# Mimi_layout.net
KiCad netlist of a schematic drawn in EAGLE
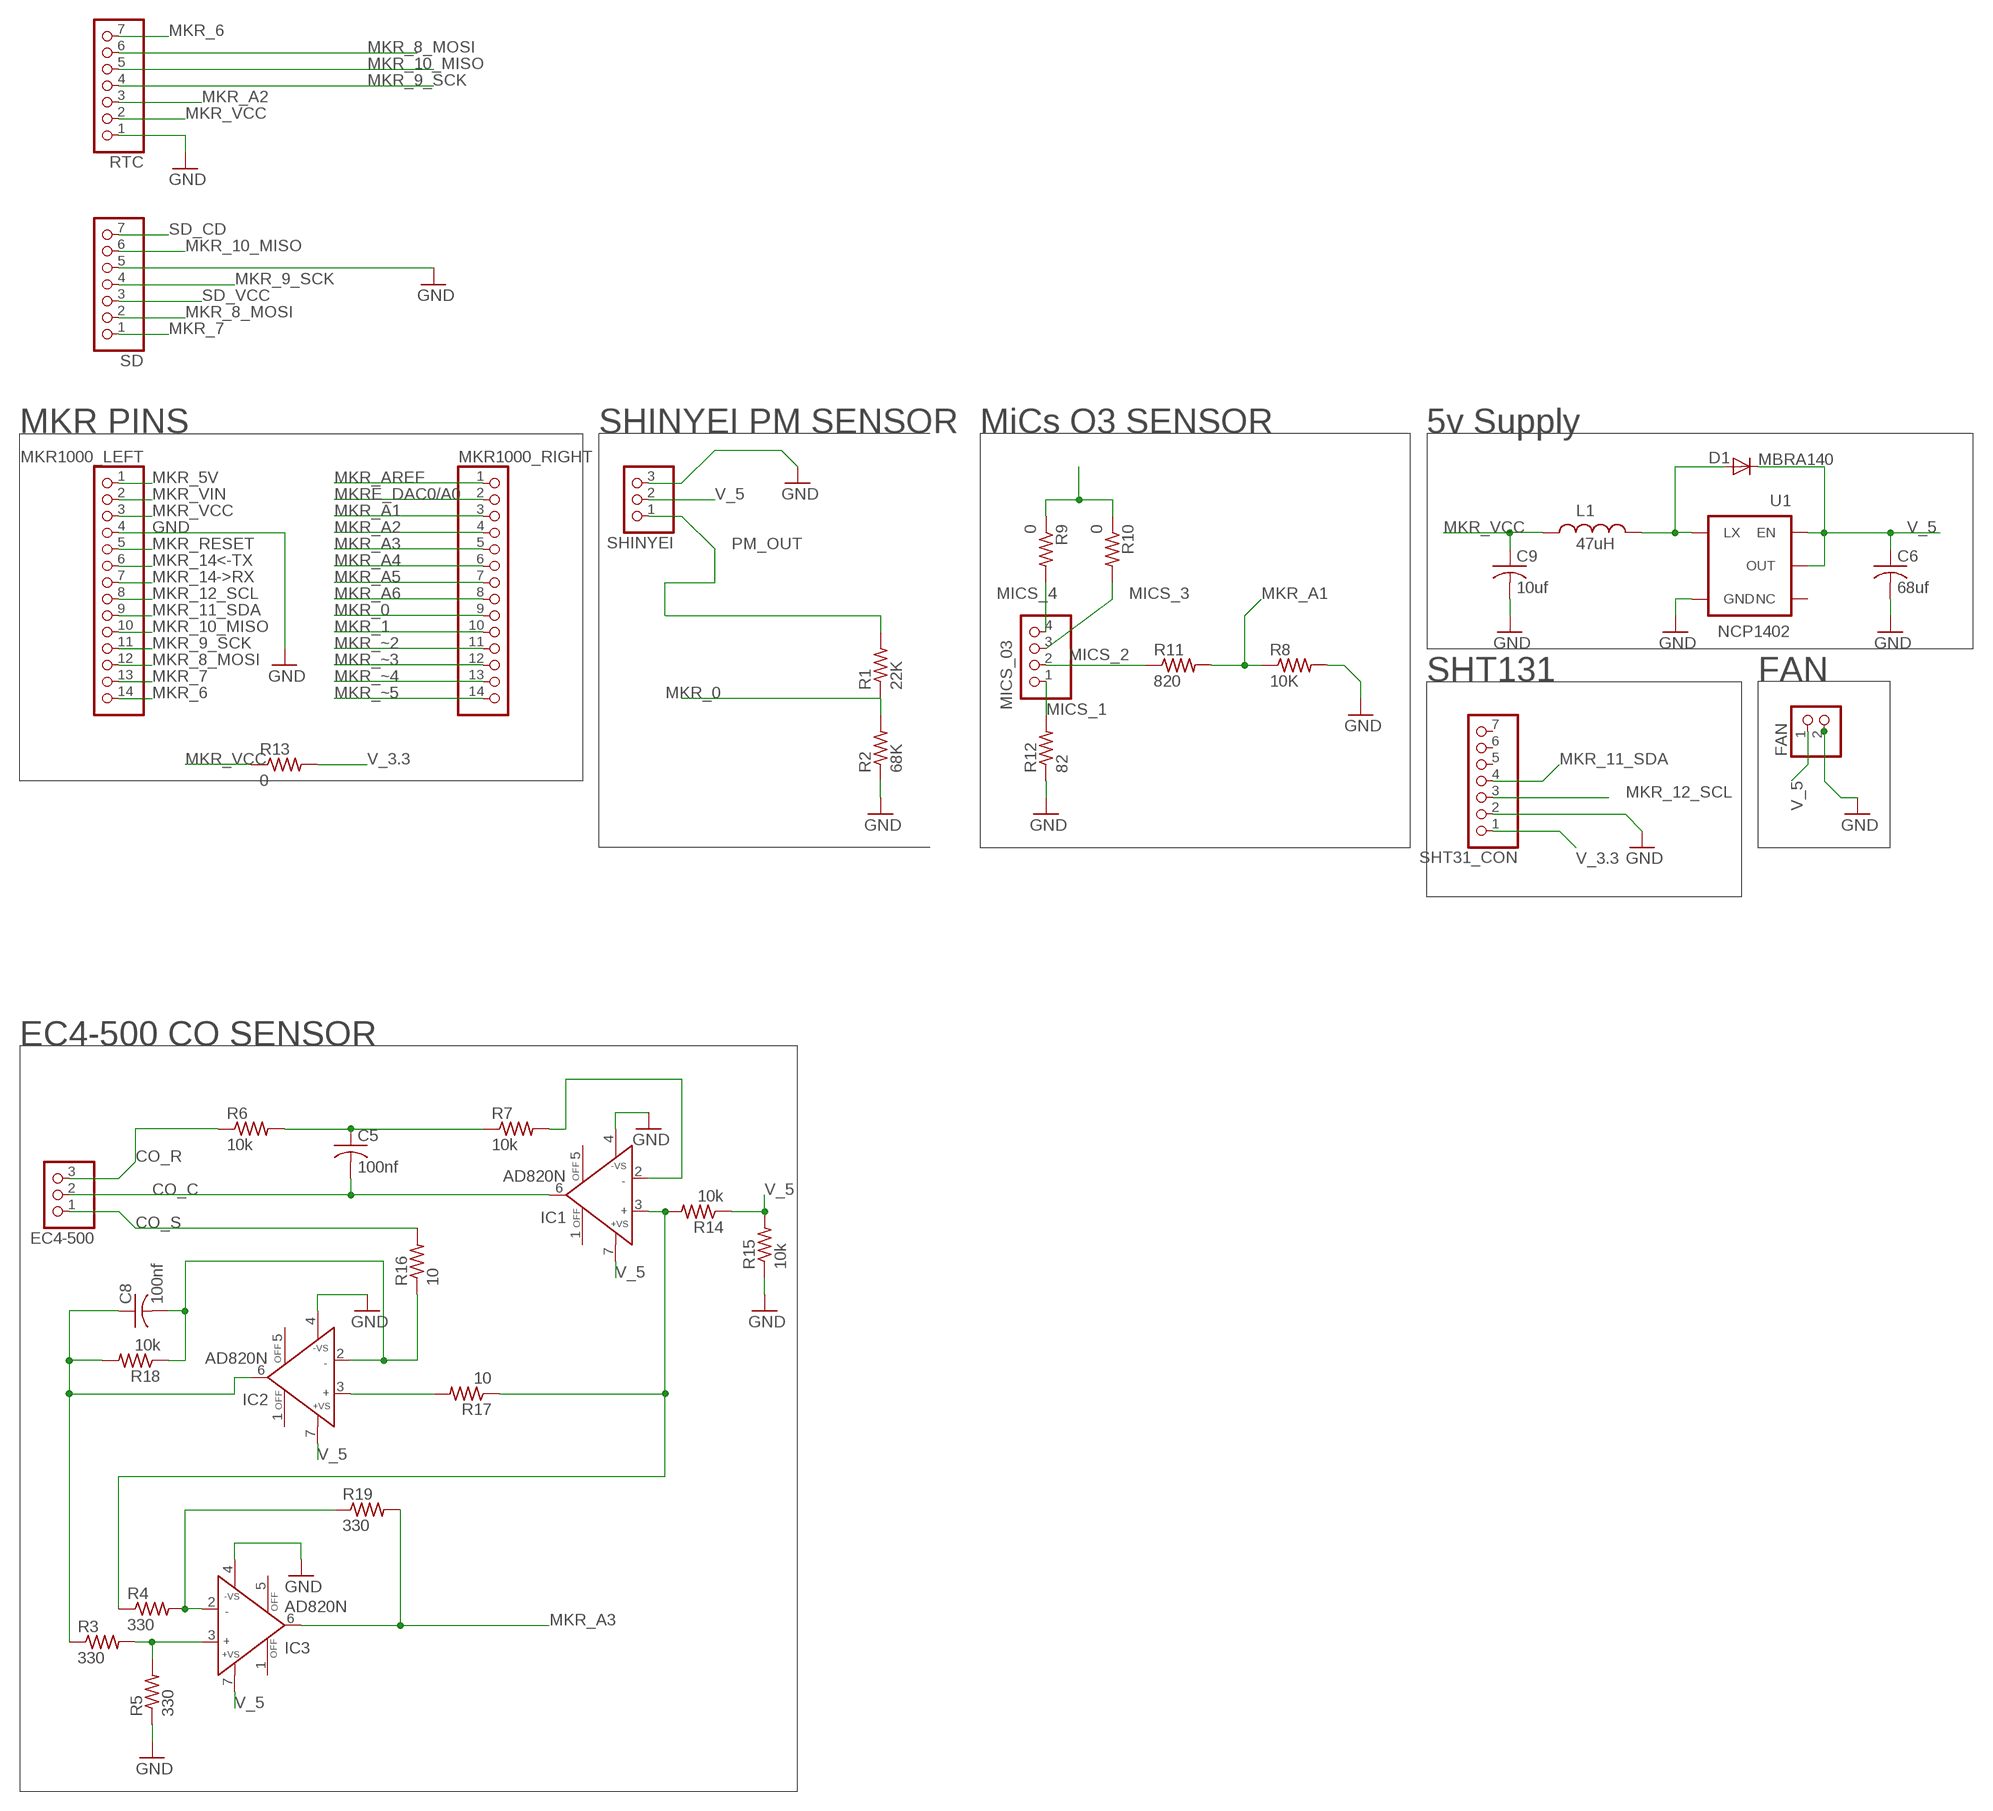
[diagram p0: schematic, sheet 1]

(export (version "E")
  (design (tool "Eeschema 10.0.6"))
  (components
    (comp (ref "C5")
      (value "100nf")
      (footprint "eagle-import:C0805")
      (libsource (lib "eagle-import") (part "C-USC0805"))
    )
    (comp (ref "C6")
      (value "68uf")
      (footprint "eagle-import:C0805")
      (libsource (lib "eagle-import") (part "C-USC0805"))
    )
    (comp (ref "C8")
      (value "100nf")
      (footprint "eagle-import:C0805")
      (libsource (lib "eagle-import") (part "C-USC0805"))
    )
    (comp (ref "C9")
      (value "10uf")
      (footprint "eagle-import:C0805")
      (libsource (lib "eagle-import") (part "C-USC0805"))
    )
    (comp (ref "D1")
      (value "MBRA140")
      (footprint "eagle-import:SMA-DIODE")
      (libsource (lib "eagle-import") (part "DIODESMA"))
    )
    (comp (ref "EC4-500")
      (value "PINHD-1X3")
      (footprint "eagle-import:1X03")
      (libsource (lib "eagle-import") (part "PINHD-1X3"))
    )
    (comp (ref "FAN")
      (value "PINHD-1X2")
      (footprint "eagle-import:1X02")
      (libsource (lib "eagle-import") (part "PINHD-1X2"))
    )
    (comp (ref "IC1")
      (value "AD820N")
      (footprint "eagle-import:DIL08")
      (libsource (lib "eagle-import") (part "AD820N"))
    )
    (comp (ref "IC2")
      (value "AD820N")
      (footprint "eagle-import:DIL08")
      (libsource (lib "eagle-import") (part "AD820N"))
    )
    (comp (ref "IC3")
      (value "AD820N")
      (footprint "eagle-import:DIL08")
      (libsource (lib "eagle-import") (part "AD820N"))
    )
    (comp (ref "L1")
      (value "47uH")
      (footprint "eagle-import:CR54")
      (libsource (lib "eagle-import") (part "INDUCTORCR54"))
    )
    (comp (ref "MICS_03")
      (value "PINHD-1X4")
      (footprint "eagle-import:1X04")
      (libsource (lib "eagle-import") (part "PINHD-1X4"))
    )
    (comp (ref "MKR1000_LEFT")
      (value "PINHD-1X14")
      (footprint "eagle-import:1X14")
      (libsource (lib "eagle-import") (part "PINHD-1X14"))
    )
    (comp (ref "MKR1000_RIGHT")
      (value "PINHD-1X14")
      (footprint "eagle-import:1X14")
      (libsource (lib "eagle-import") (part "PINHD-1X14"))
    )
    (comp (ref "R1")
      (value "22K")
      (footprint "eagle-import:R0805")
      (libsource (lib "eagle-import") (part "R-US_R0805"))
    )
    (comp (ref "R2")
      (value "68K")
      (footprint "eagle-import:R0805")
      (libsource (lib "eagle-import") (part "R-US_R0805"))
    )
    (comp (ref "R3")
      (value "330")
      (footprint "eagle-import:R0805")
      (libsource (lib "eagle-import") (part "R-US_R0805"))
    )
    (comp (ref "R4")
      (value "330")
      (footprint "eagle-import:R0805")
      (libsource (lib "eagle-import") (part "R-US_R0805"))
    )
    (comp (ref "R5")
      (value "330")
      (footprint "eagle-import:R0805")
      (libsource (lib "eagle-import") (part "R-US_R0805"))
    )
    (comp (ref "R6")
      (value "10k")
      (footprint "eagle-import:R0805")
      (libsource (lib "eagle-import") (part "R-US_R0805"))
    )
    (comp (ref "R7")
      (value "10k")
      (footprint "eagle-import:R0805")
      (libsource (lib "eagle-import") (part "R-US_R0805"))
    )
    (comp (ref "R8")
      (value "10K")
      (footprint "eagle-import:R0805")
      (libsource (lib "eagle-import") (part "R-US_R0805"))
    )
    (comp (ref "R9")
      (value "0")
      (footprint "eagle-import:R0805")
      (libsource (lib "eagle-import") (part "R-US_R0805"))
    )
    (comp (ref "R10")
      (value "0")
      (footprint "eagle-import:R0805")
      (libsource (lib "eagle-import") (part "R-US_R0805"))
    )
    (comp (ref "R11")
      (value "820")
      (footprint "eagle-import:R0805")
      (libsource (lib "eagle-import") (part "R-US_R0805"))
    )
    (comp (ref "R12")
      (value "82")
      (footprint "eagle-import:R0805")
      (libsource (lib "eagle-import") (part "R-US_R0805"))
    )
    (comp (ref "R13")
      (value "0")
      (footprint "eagle-import:R0805")
      (libsource (lib "eagle-import") (part "R-US_R0805"))
    )
    (comp (ref "R14")
      (value "10k")
      (footprint "eagle-import:R0805")
      (libsource (lib "eagle-import") (part "R-US_R0805"))
    )
    (comp (ref "R15")
      (value "10k")
      (footprint "eagle-import:R0805")
      (libsource (lib "eagle-import") (part "R-US_R0805"))
    )
    (comp (ref "R16")
      (value "10")
      (footprint "eagle-import:R0805")
      (libsource (lib "eagle-import") (part "R-US_R0805"))
    )
    (comp (ref "R17")
      (value "10")
      (footprint "eagle-import:R0805")
      (libsource (lib "eagle-import") (part "R-US_R0805"))
    )
    (comp (ref "R18")
      (value "10k")
      (footprint "eagle-import:R0805")
      (libsource (lib "eagle-import") (part "R-US_R0805"))
    )
    (comp (ref "R19")
      (value "330")
      (footprint "eagle-import:R0805")
      (libsource (lib "eagle-import") (part "R-US_R0805"))
    )
    (comp (ref "RTC")
      (value "PINHD-1X7")
      (footprint "eagle-import:1X07")
      (libsource (lib "eagle-import") (part "PINHD-1X7"))
    )
    (comp (ref "SD")
      (value "PINHD-1X7")
      (footprint "eagle-import:1X07")
      (libsource (lib "eagle-import") (part "PINHD-1X7"))
    )
    (comp (ref "SHINYEI")
      (value "PINHD-1X3")
      (footprint "eagle-import:1X03")
      (libsource (lib "eagle-import") (part "PINHD-1X3"))
    )
    (comp (ref "SHT31_CON")
      (value "PINHD-1X7")
      (footprint "eagle-import:1X07")
      (libsource (lib "eagle-import") (part "PINHD-1X7"))
    )
    (comp (ref "U1")
      (value "NCP1402")
      (footprint "eagle-import:SOT23-5")
      (libsource (lib "eagle-import") (part "V_REG_NCP1400SOT23-5"))
    )
  )
  (nets
    (net (code "1") (name "/CO_C") (class "Default")
      (node (ref "C5") (pin "2") (pinfunction "2_2") (pintype "passive"))
      (node (ref "EC4-500") (pin "2") (pinfunction "2_2") (pintype "passive"))
      (node (ref "IC1") (pin "6") (pinfunction "OUT_6") (pintype "output"))
    )
    (net (code "2") (name "/CO_R") (class "Default")
      (node (ref "EC4-500") (pin "3") (pinfunction "3_3") (pintype "passive"))
      (node (ref "R6") (pin "1") (pinfunction "1_1") (pintype "passive"))
    )
    (net (code "3") (name "/CO_S") (class "Default")
      (node (ref "EC4-500") (pin "1") (pinfunction "1_1") (pintype "passive"))
      (node (ref "R16") (pin "2") (pinfunction "2_2") (pintype "passive"))
    )
    (net (code "4") (name "/MICS_1") (class "Default")
      (node (ref "MICS_03") (pin "1") (pinfunction "1_1") (pintype "passive"))
      (node (ref "R12") (pin "2") (pinfunction "2_2") (pintype "passive"))
    )
    (net (code "5") (name "/MICS_2") (class "Default")
      (node (ref "MICS_03") (pin "2") (pinfunction "2_2") (pintype "passive"))
      (node (ref "R11") (pin "1") (pinfunction "1_1") (pintype "passive"))
    )
    (net (code "6") (name "/MICS_3") (class "Default")
      (node (ref "MICS_03") (pin "3") (pinfunction "3_3") (pintype "passive"))
      (node (ref "R10") (pin "2") (pinfunction "2_2") (pintype "passive"))
    )
    (net (code "7") (name "/MICS_4") (class "Default")
      (node (ref "MICS_03") (pin "4") (pinfunction "4_4") (pintype "passive"))
      (node (ref "R9") (pin "2") (pinfunction "2_2") (pintype "passive"))
    )
    (net (code "8") (name "/MKRE_DAC0{slash}A0") (class "Default")
      (node (ref "MKR1000_RIGHT") (pin "2") (pinfunction "2_2") (pintype "passive"))
    )
    (net (code "9") (name "/MKR_0") (class "Default")
      (node (ref "MKR1000_RIGHT") (pin "9") (pinfunction "9_9") (pintype "passive"))
      (node (ref "R1") (pin "1") (pinfunction "1_1") (pintype "passive"))
      (node (ref "R2") (pin "2") (pinfunction "2_2") (pintype "passive"))
    )
    (net (code "10") (name "/MKR_1") (class "Default")
      (node (ref "MKR1000_RIGHT") (pin "10") (pinfunction "10_10") (pintype "passive"))
    )
    (net (code "11") (name "/MKR_5V") (class "Default")
      (node (ref "MKR1000_LEFT") (pin "1") (pinfunction "1_1") (pintype "passive"))
    )
    (net (code "12") (name "/MKR_6") (class "Default")
      (node (ref "MKR1000_LEFT") (pin "14") (pinfunction "14_14") (pintype "passive"))
      (node (ref "RTC") (pin "7") (pinfunction "7_7") (pintype "passive"))
    )
    (net (code "13") (name "/MKR_7") (class "Default")
      (node (ref "MKR1000_LEFT") (pin "13") (pinfunction "13_13") (pintype "passive"))
      (node (ref "SD") (pin "1") (pinfunction "1_1") (pintype "passive"))
    )
    (net (code "14") (name "/MKR_8_MOSI") (class "Default")
      (node (ref "MKR1000_LEFT") (pin "12") (pinfunction "12_12") (pintype "passive"))
      (node (ref "RTC") (pin "6") (pinfunction "6_6") (pintype "passive"))
      (node (ref "SD") (pin "2") (pinfunction "2_2") (pintype "passive"))
    )
    (net (code "15") (name "/MKR_9_SCK") (class "Default")
      (node (ref "MKR1000_LEFT") (pin "11") (pinfunction "11_11") (pintype "passive"))
      (node (ref "RTC") (pin "4") (pinfunction "4_4") (pintype "passive"))
      (node (ref "SD") (pin "4") (pinfunction "4_4") (pintype "passive"))
    )
    (net (code "16") (name "/MKR_10_MISO") (class "Default")
      (node (ref "MKR1000_LEFT") (pin "10") (pinfunction "10_10") (pintype "passive"))
      (node (ref "RTC") (pin "5") (pinfunction "5_5") (pintype "passive"))
      (node (ref "SD") (pin "6") (pinfunction "6_6") (pintype "passive"))
    )
    (net (code "17") (name "/MKR_11_SDA") (class "Default")
      (node (ref "MKR1000_LEFT") (pin "9") (pinfunction "9_9") (pintype "passive"))
      (node (ref "SHT31_CON") (pin "4") (pinfunction "4_4") (pintype "passive"))
    )
    (net (code "18") (name "/MKR_12_SCL") (class "Default")
      (node (ref "MKR1000_LEFT") (pin "8") (pinfunction "8_8") (pintype "passive"))
      (node (ref "SHT31_CON") (pin "3") (pinfunction "3_3") (pintype "passive"))
    )
    (net (code "19") (name "/MKR_14->RX") (class "Default")
      (node (ref "MKR1000_LEFT") (pin "7") (pinfunction "7_7") (pintype "passive"))
    )
    (net (code "20") (name "/MKR_14<-TX") (class "Default")
      (node (ref "MKR1000_LEFT") (pin "6") (pinfunction "6_6") (pintype "passive"))
    )
    (net (code "21") (name "/MKR_A1") (class "Default")
      (node (ref "MKR1000_RIGHT") (pin "3") (pinfunction "3_3") (pintype "passive"))
      (node (ref "R11") (pin "2") (pinfunction "2_2") (pintype "passive"))
      (node (ref "R8") (pin "1") (pinfunction "1_1") (pintype "passive"))
    )
    (net (code "22") (name "/MKR_A2") (class "Default")
      (node (ref "MKR1000_RIGHT") (pin "4") (pinfunction "4_4") (pintype "passive"))
      (node (ref "RTC") (pin "3") (pinfunction "3_3") (pintype "passive"))
    )
    (net (code "23") (name "/MKR_A3") (class "Default")
      (node (ref "IC3") (pin "6") (pinfunction "OUT_6") (pintype "output"))
      (node (ref "MKR1000_RIGHT") (pin "5") (pinfunction "5_5") (pintype "passive"))
      (node (ref "R19") (pin "2") (pinfunction "2_2") (pintype "passive"))
    )
    (net (code "24") (name "/MKR_A4") (class "Default")
      (node (ref "MKR1000_RIGHT") (pin "6") (pinfunction "6_6") (pintype "passive"))
    )
    (net (code "25") (name "/MKR_A5") (class "Default")
      (node (ref "MKR1000_RIGHT") (pin "7") (pinfunction "7_7") (pintype "passive"))
    )
    (net (code "26") (name "/MKR_A6") (class "Default")
      (node (ref "MKR1000_RIGHT") (pin "8") (pinfunction "8_8") (pintype "passive"))
    )
    (net (code "27") (name "/MKR_AREF") (class "Default")
      (node (ref "MKR1000_RIGHT") (pin "1") (pinfunction "1_1") (pintype "passive"))
    )
    (net (code "28") (name "/MKR_RESET") (class "Default")
      (node (ref "MKR1000_LEFT") (pin "5") (pinfunction "5_5") (pintype "passive"))
    )
    (net (code "29") (name "/MKR_VCC") (class "Default")
      (node (ref "C9") (pin "1") (pinfunction "1_1") (pintype "passive"))
      (node (ref "L1") (pin "P$1") (pinfunction "1_P$1") (pintype "passive"))
      (node (ref "MKR1000_LEFT") (pin "3") (pinfunction "3_3") (pintype "passive"))
      (node (ref "R13") (pin "1") (pinfunction "1_1") (pintype "passive"))
      (node (ref "RTC") (pin "2") (pinfunction "2_2") (pintype "passive"))
    )
    (net (code "30") (name "/MKR_VIN") (class "Default")
      (node (ref "MKR1000_LEFT") (pin "2") (pinfunction "2_2") (pintype "passive"))
    )
    (net (code "31") (name "/MKR_~{2}") (class "Default")
      (node (ref "MKR1000_RIGHT") (pin "11") (pinfunction "11_11") (pintype "passive"))
    )
    (net (code "32") (name "/MKR_~{3}") (class "Default")
      (node (ref "MKR1000_RIGHT") (pin "12") (pinfunction "12_12") (pintype "passive"))
    )
    (net (code "33") (name "/MKR_~{4}") (class "Default")
      (node (ref "MKR1000_RIGHT") (pin "13") (pinfunction "13_13") (pintype "passive"))
    )
    (net (code "34") (name "/MKR_~{5}") (class "Default")
      (node (ref "MKR1000_RIGHT") (pin "14") (pinfunction "14_14") (pintype "passive"))
    )
    (net (code "35") (name "/PM_OUT") (class "Default")
      (node (ref "R1") (pin "2") (pinfunction "2_2") (pintype "passive"))
      (node (ref "SHINYEI") (pin "1") (pinfunction "1_1") (pintype "passive"))
    )
    (net (code "36") (name "/SD_CD") (class "Default")
      (node (ref "SD") (pin "7") (pinfunction "7_7") (pintype "passive"))
    )
    (net (code "37") (name "/SD_VCC") (class "Default")
      (node (ref "SD") (pin "3") (pinfunction "3_3") (pintype "passive"))
    )
    (net (code "38") (name "/V_3.3") (class "Default")
      (node (ref "R13") (pin "2") (pinfunction "2_2") (pintype "passive"))
      (node (ref "SHT31_CON") (pin "1") (pinfunction "1_1") (pintype "passive"))
    )
    (net (code "39") (name "/V_5") (class "Default")
      (node (ref "C6") (pin "1") (pinfunction "1_1") (pintype "passive"))
      (node (ref "D1") (pin "C") (pinfunction "C_C") (pintype "passive"))
      (node (ref "FAN") (pin "1") (pinfunction "1_1") (pintype "passive"))
      (node (ref "IC1") (pin "7") (pinfunction "+VS_7") (pintype "input"))
      (node (ref "IC2") (pin "7") (pinfunction "+VS_7") (pintype "input"))
      (node (ref "IC3") (pin "7") (pinfunction "+VS_7") (pintype "input"))
      (node (ref "R10") (pin "1") (pinfunction "1_1") (pintype "passive"))
      (node (ref "R14") (pin "1") (pinfunction "1_1") (pintype "passive"))
      (node (ref "R15") (pin "2") (pinfunction "2_2") (pintype "passive"))
      (node (ref "R9") (pin "1") (pinfunction "1_1") (pintype "passive"))
      (node (ref "SHINYEI") (pin "2") (pinfunction "2_2") (pintype "passive"))
      (node (ref "U1") (pin "1") (pinfunction "EN_1") (pintype "input"))
      (node (ref "U1") (pin "2") (pinfunction "OUT_2") (pintype "passive"))
    )
    (net (code "40") (name "GND") (class "Default")
      (node (ref "C6") (pin "2") (pinfunction "2_2") (pintype "passive"))
      (node (ref "C9") (pin "2") (pinfunction "2_2") (pintype "passive"))
      (node (ref "FAN") (pin "2") (pinfunction "2_2") (pintype "passive"))
      (node (ref "IC1") (pin "4") (pinfunction "-VS_4") (pintype "input"))
      (node (ref "IC2") (pin "4") (pinfunction "-VS_4") (pintype "input"))
      (node (ref "IC3") (pin "4") (pinfunction "-VS_4") (pintype "input"))
      (node (ref "MKR1000_LEFT") (pin "4") (pinfunction "4_4") (pintype "passive"))
      (node (ref "R12") (pin "1") (pinfunction "1_1") (pintype "passive"))
      (node (ref "R15") (pin "1") (pinfunction "1_1") (pintype "passive"))
      (node (ref "R2") (pin "1") (pinfunction "1_1") (pintype "passive"))
      (node (ref "R5") (pin "1") (pinfunction "1_1") (pintype "passive"))
      (node (ref "R8") (pin "2") (pinfunction "2_2") (pintype "passive"))
      (node (ref "RTC") (pin "1") (pinfunction "1_1") (pintype "passive"))
      (node (ref "SD") (pin "5") (pinfunction "5_5") (pintype "passive"))
      (node (ref "SHINYEI") (pin "3") (pinfunction "3_3") (pintype "passive"))
      (node (ref "SHT31_CON") (pin "2") (pinfunction "2_2") (pintype "passive"))
      (node (ref "U1") (pin "4") (pinfunction "GND_4") (pintype "input"))
    )
    (net (code "41") (name "Net-(C5-Pad1)") (class "Default")
      (node (ref "C5") (pin "1") (pinfunction "1_1") (pintype "passive"))
      (node (ref "R6") (pin "2") (pinfunction "2_2") (pintype "passive"))
      (node (ref "R7") (pin "1") (pinfunction "1_1") (pintype "passive"))
    )
    (net (code "42") (name "Net-(IC1-IN+)") (class "Default")
      (node (ref "IC1") (pin "3") (pinfunction "IN+_3") (pintype "input"))
      (node (ref "R14") (pin "2") (pinfunction "2_2") (pintype "passive"))
      (node (ref "R17") (pin "1") (pinfunction "1_1") (pintype "passive"))
      (node (ref "R4") (pin "1") (pinfunction "1_1") (pintype "passive"))
    )
    (net (code "43") (name "Net-(IC1-IN-)") (class "Default")
      (node (ref "IC1") (pin "2") (pinfunction "IN-_2") (pintype "input"))
      (node (ref "R7") (pin "2") (pinfunction "2_2") (pintype "passive"))
    )
    (net (code "44") (name "Net-(IC2-IN+)") (class "Default")
      (node (ref "IC2") (pin "3") (pinfunction "IN+_3") (pintype "input"))
      (node (ref "R17") (pin "2") (pinfunction "2_2") (pintype "passive"))
    )
    (net (code "45") (name "Net-(IC2-IN-)") (class "Default")
      (node (ref "C8") (pin "2") (pinfunction "2_2") (pintype "passive"))
      (node (ref "IC2") (pin "2") (pinfunction "IN-_2") (pintype "input"))
      (node (ref "R16") (pin "1") (pinfunction "1_1") (pintype "passive"))
      (node (ref "R18") (pin "1") (pinfunction "1_1") (pintype "passive"))
    )
    (net (code "46") (name "Net-(IC2-OUT)") (class "Default")
      (node (ref "C8") (pin "1") (pinfunction "1_1") (pintype "passive"))
      (node (ref "IC2") (pin "6") (pinfunction "OUT_6") (pintype "output"))
      (node (ref "R18") (pin "2") (pinfunction "2_2") (pintype "passive"))
      (node (ref "R3") (pin "1") (pinfunction "1_1") (pintype "passive"))
    )
    (net (code "47") (name "Net-(IC3-IN+)") (class "Default")
      (node (ref "IC3") (pin "3") (pinfunction "IN+_3") (pintype "input"))
      (node (ref "R3") (pin "2") (pinfunction "2_2") (pintype "passive"))
      (node (ref "R5") (pin "2") (pinfunction "2_2") (pintype "passive"))
    )
    (net (code "48") (name "Net-(IC3-IN-)") (class "Default")
      (node (ref "IC3") (pin "2") (pinfunction "IN-_2") (pintype "input"))
      (node (ref "R19") (pin "1") (pinfunction "1_1") (pintype "passive"))
      (node (ref "R4") (pin "2") (pinfunction "2_2") (pintype "passive"))
    )
    (net (code "49") (name "Net-(L1-2)") (class "Default")
      (node (ref "D1") (pin "A") (pinfunction "A_A") (pintype "passive"))
      (node (ref "L1") (pin "P$2") (pinfunction "2_P$2") (pintype "passive"))
      (node (ref "U1") (pin "5") (pinfunction "LX_5") (pintype "input"))
    )
    (net (code "50") (name "unconnected-(IC1-OFF-Pad1)") (class "Default")
      (node (ref "IC1") (pin "1") (pinfunction "OFF_1") (pintype "passive"))
    )
    (net (code "51") (name "unconnected-(IC1-OFF-Pad5)") (class "Default")
      (node (ref "IC1") (pin "5") (pinfunction "OFF_5") (pintype "passive"))
    )
    (net (code "52") (name "unconnected-(IC2-OFF-Pad1)") (class "Default")
      (node (ref "IC2") (pin "1") (pinfunction "OFF_1") (pintype "passive"))
    )
    (net (code "53") (name "unconnected-(IC2-OFF-Pad5)") (class "Default")
      (node (ref "IC2") (pin "5") (pinfunction "OFF_5") (pintype "passive"))
    )
    (net (code "54") (name "unconnected-(IC3-OFF-Pad1)") (class "Default")
      (node (ref "IC3") (pin "1") (pinfunction "OFF_1") (pintype "passive"))
    )
    (net (code "55") (name "unconnected-(IC3-OFF-Pad5)") (class "Default")
      (node (ref "IC3") (pin "5") (pinfunction "OFF_5") (pintype "passive"))
    )
    (net (code "56") (name "unconnected-(SHT31_CON-Pad5)") (class "Default")
      (node (ref "SHT31_CON") (pin "5") (pinfunction "5_5") (pintype "passive"))
    )
    (net (code "57") (name "unconnected-(SHT31_CON-Pad6)") (class "Default")
      (node (ref "SHT31_CON") (pin "6") (pinfunction "6_6") (pintype "passive"))
    )
    (net (code "58") (name "unconnected-(SHT31_CON-Pad7)") (class "Default")
      (node (ref "SHT31_CON") (pin "7") (pinfunction "7_7") (pintype "passive"))
    )
    (net (code "59") (name "unconnected-(U1-NC-Pad3)") (class "Default")
      (node (ref "U1") (pin "3") (pinfunction "NC_3") (pintype "input"))
    )
  )
)
